# MCU.net
KiCad netlist of a schematic drawn in Altium Designer
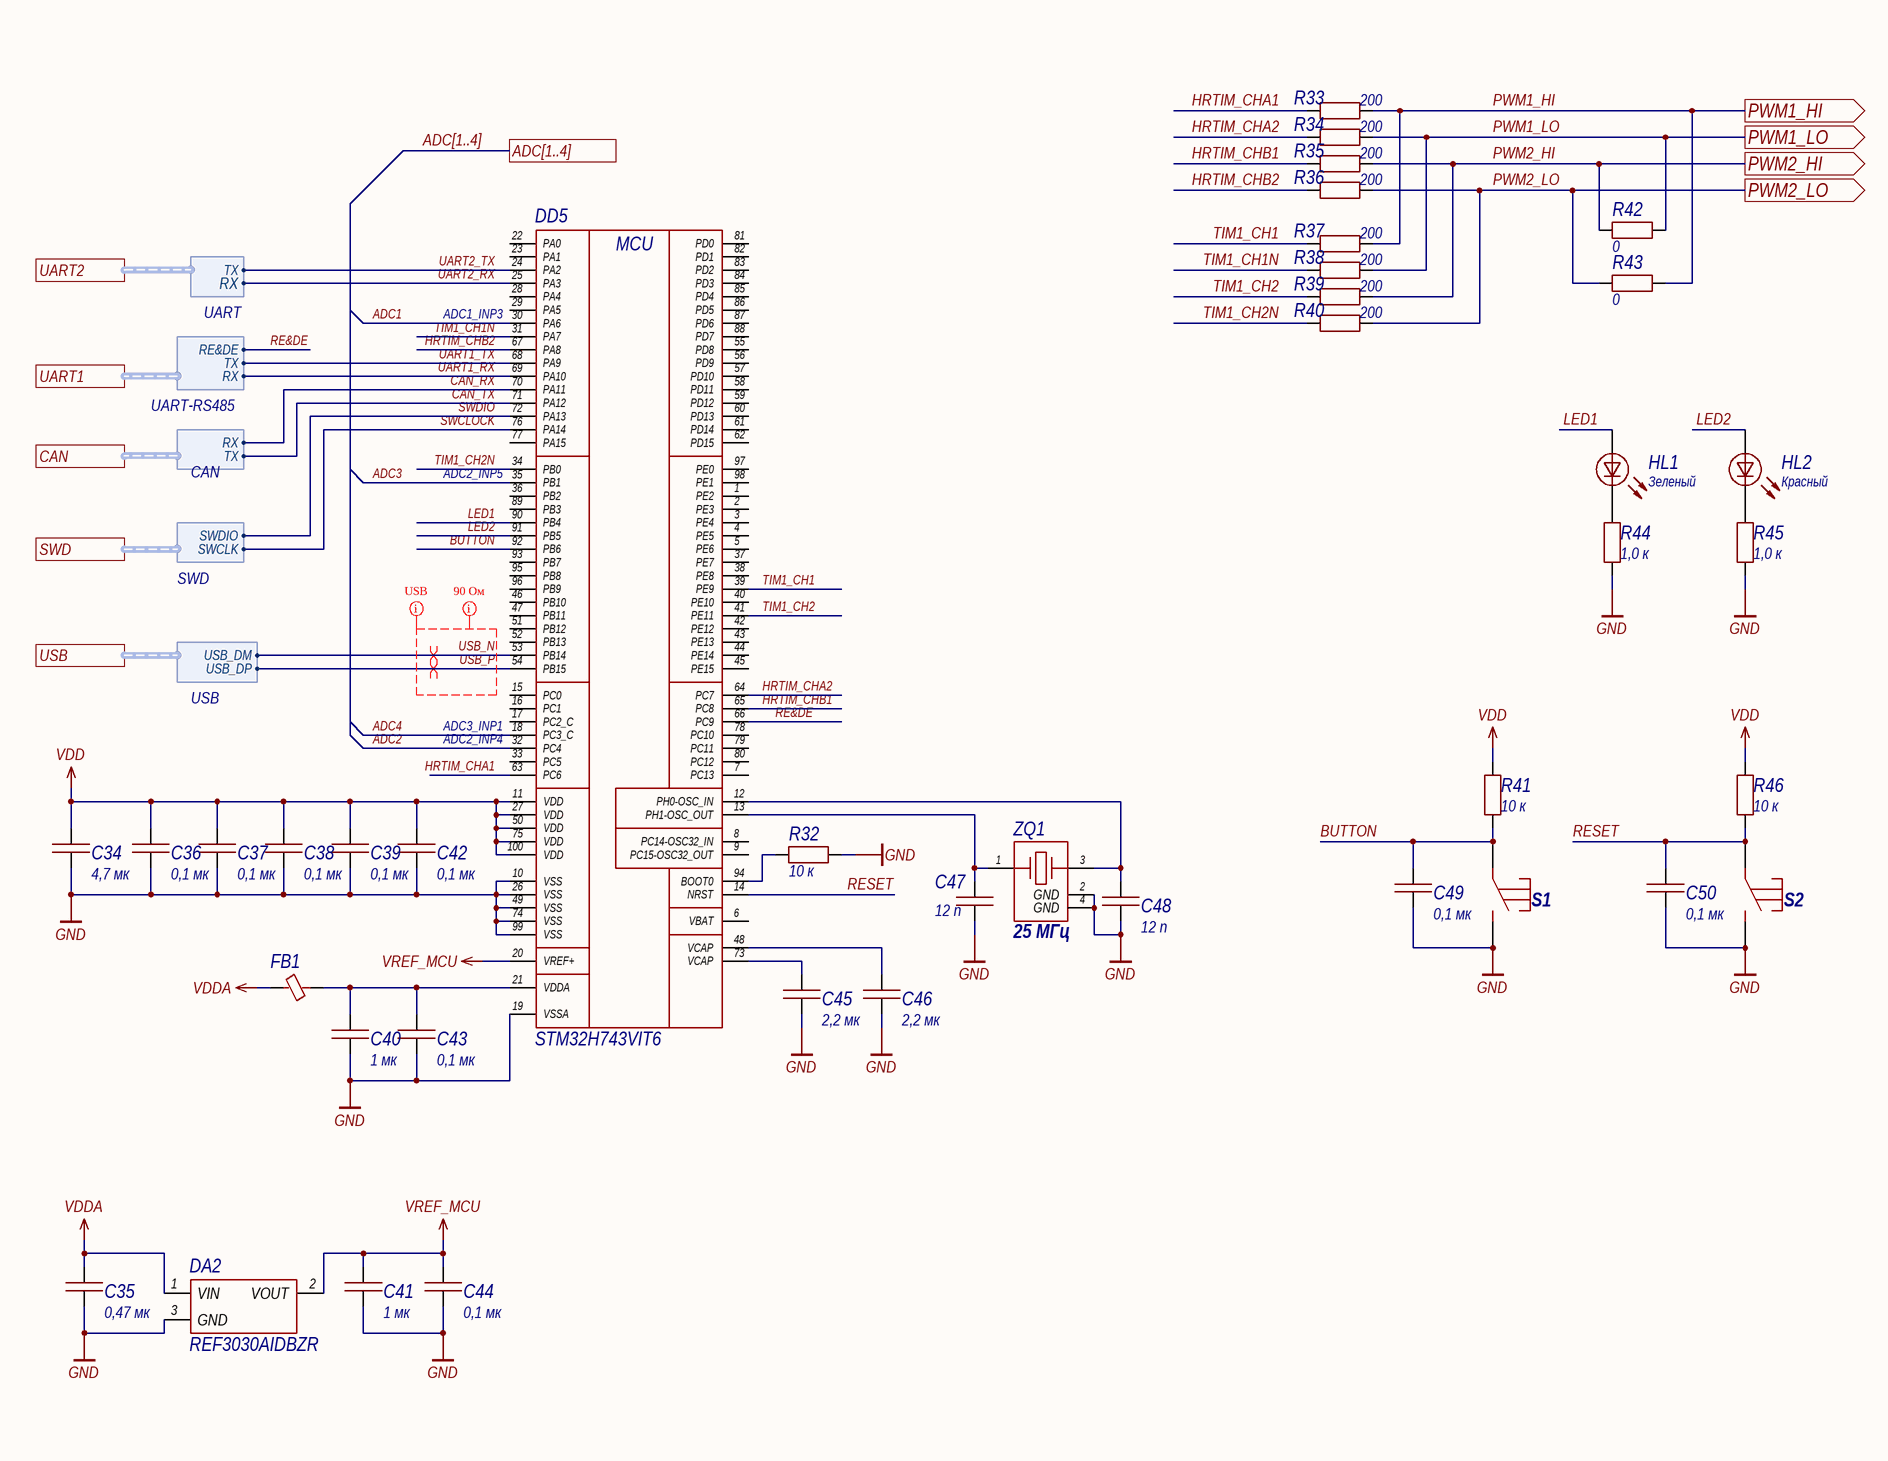
[diagram p0: MCU.SchDoc, left]
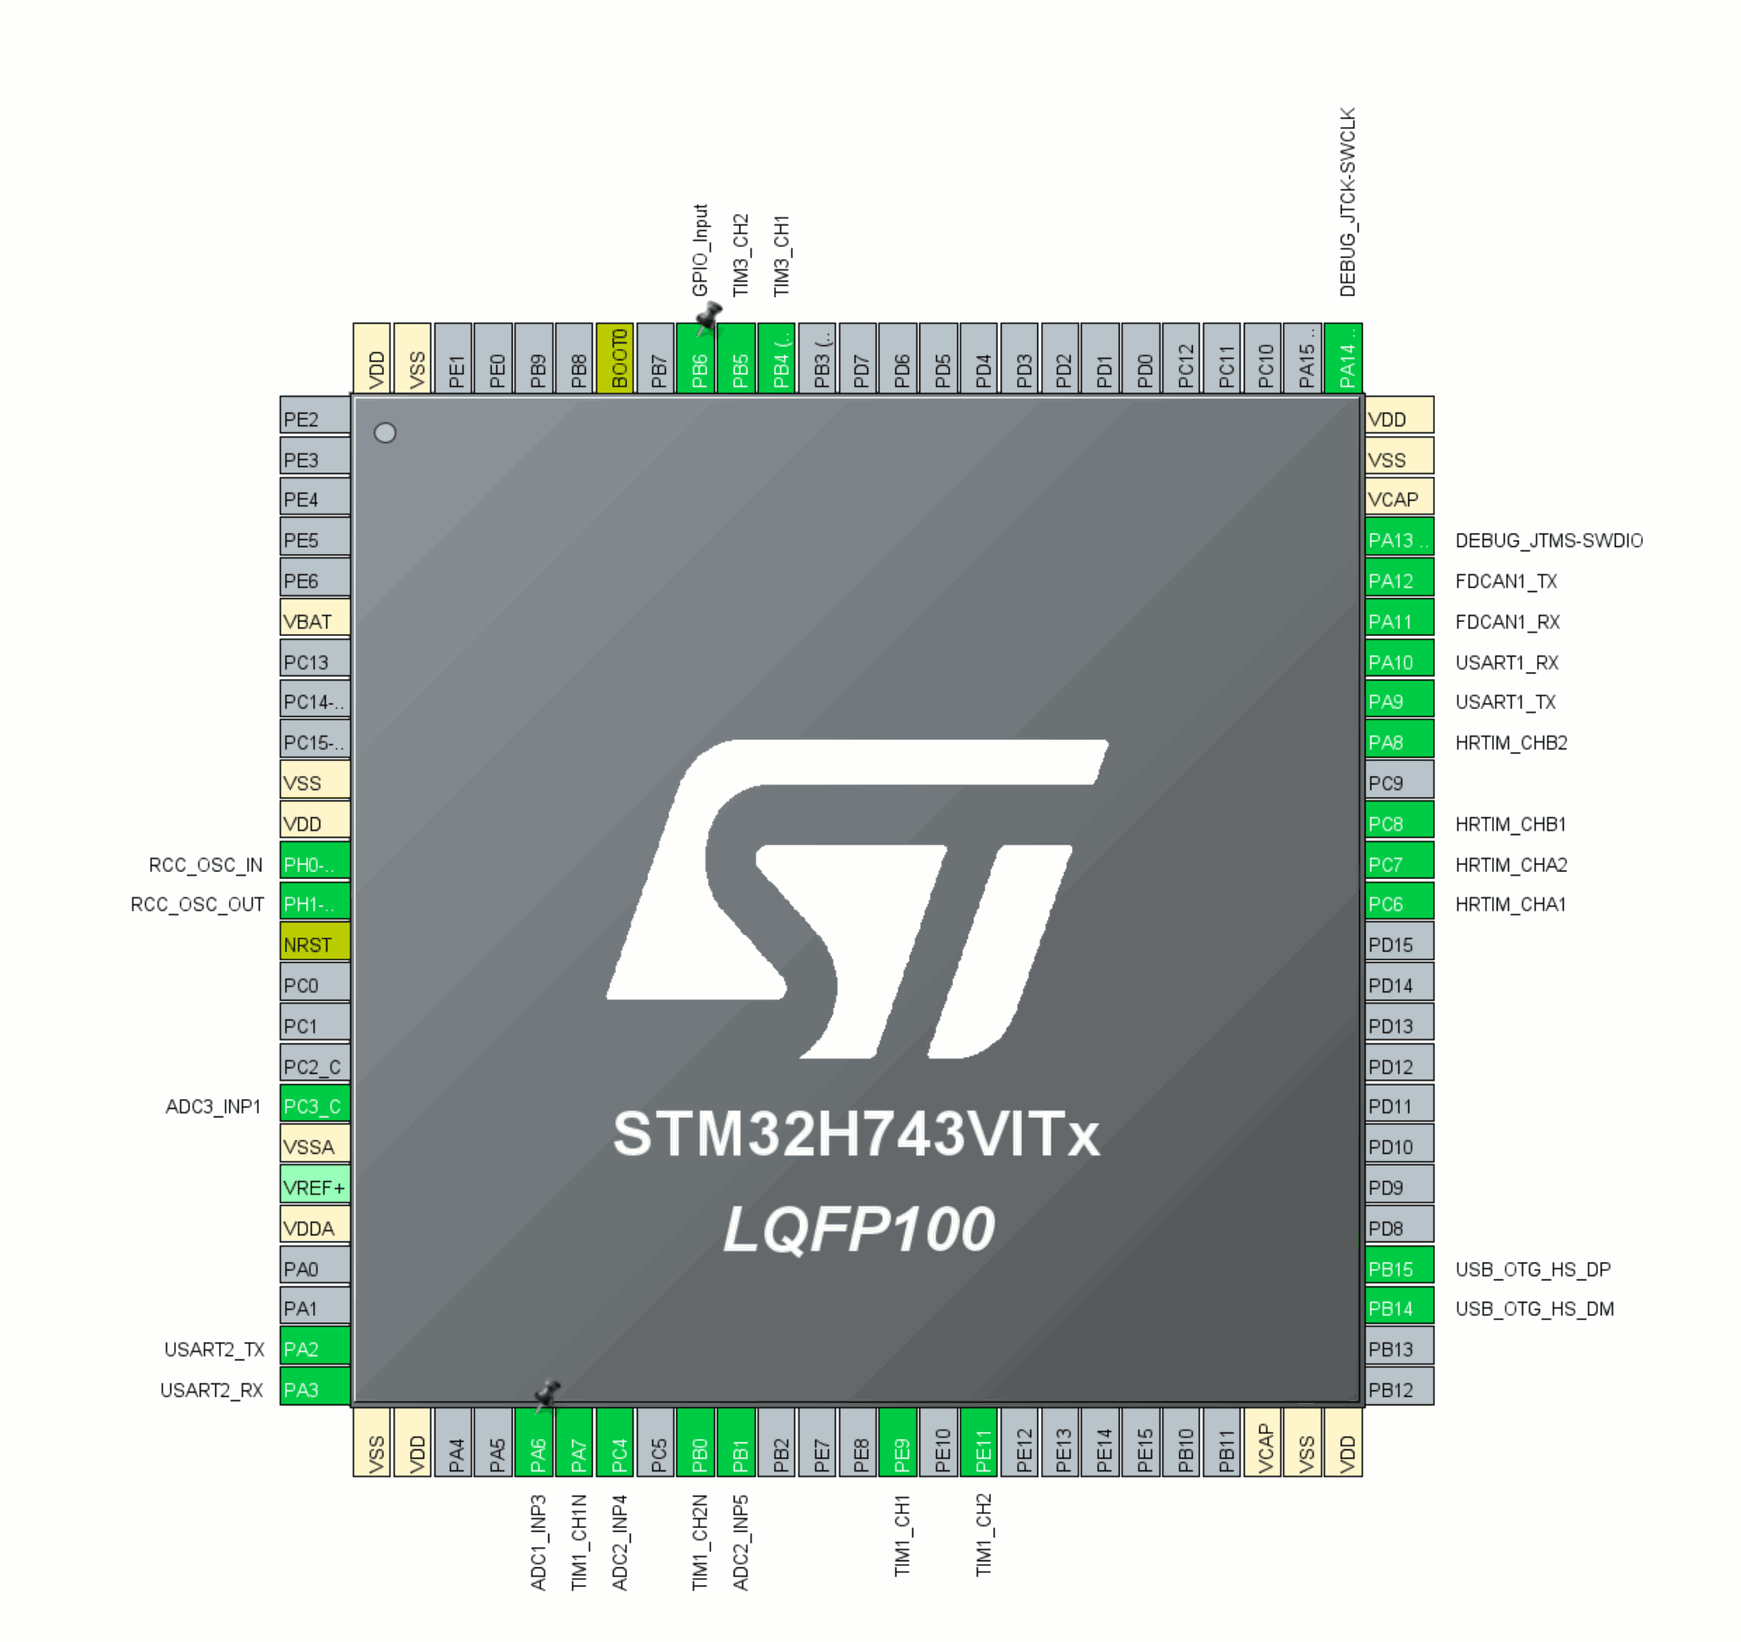
[diagram p1: MCU.SchDoc, right]

(export (version "E")
  (design (tool "Eeschema 10.0.6"))
  (components
    (comp (ref "C34")
      (value "4,7 мк")
      (footprint "1206C")
      (description "Конденсатор 1206C ёмкостью 4,7 мк 10%, 50 В, X7R")
      (fields (field (name "PART NUMBER") "Capacitor_4,7u_10_50V_X7R_1206C") (field (name "TOLERANCE") "10%"))
      (libsource (lib "Hydrolib") (part "Capacitor"))
    )
    (comp (ref "C35")
      (value "0,47 мк")
      (footprint "0603C")
      (description "Конденсатор 0603C ёмкостью 0,47 мк 10%, 50 В, X7R")
      (fields
        (field (name "PART NUMBER") "Capacitor_0,47u_10_50V_X7R_0603C")
        (field (name "TOLERANCE") "10%")
      )
      (libsource (lib "Hydrolib") (part "Capacitor"))
    )
    (comp (ref "C36")
      (value "0,1 мк")
      (footprint "0603C")
      (description "Конденсатор 0603C ёмкостью 0,1 мк 10%, 50 В, X7R")
      (fields (field (name "PART NUMBER") "Capacitor_0,1u_10_50V_X7R_0603C") (field (name "TOLERANCE") "10%"))
      (libsource (lib "Hydrolib") (part "Capacitor"))
    )
    (comp (ref "C37")
      (value "0,1 мк")
      (footprint "0603C")
      (description "Конденсатор 0603C ёмкостью 0,1 мк 10%, 50 В, X7R")
      (fields (field (name "PART NUMBER") "Capacitor_0,1u_10_50V_X7R_0603C") (field (name "TOLERANCE") "10%"))
      (libsource (lib "Hydrolib") (part "Capacitor"))
    )
    (comp (ref "C38")
      (value "0,1 мк")
      (footprint "0603C")
      (description "Конденсатор 0603C ёмкостью 0,1 мк 10%, 50 В, X7R")
      (fields (field (name "PART NUMBER") "Capacitor_0,1u_10_50V_X7R_0603C") (field (name "TOLERANCE") "10%"))
      (libsource (lib "Hydrolib") (part "Capacitor"))
    )
    (comp (ref "C39")
      (value "0,1 мк")
      (footprint "0603C")
      (description "Конденсатор 0603C ёмкостью 0,1 мк 10%, 50 В, X7R")
      (fields (field (name "PART NUMBER") "Capacitor_0,1u_10_50V_X7R_0603C") (field (name "TOLERANCE") "10%"))
      (libsource (lib "Hydrolib") (part "Capacitor"))
    )
    (comp (ref "C40")
      (value "1 мк")
      (footprint "0603C")
      (description "Конденсатор 0603C ёмкостью 1 мк 10%, 25 В, X7R")
      (fields (field (name "PART NUMBER") "Capacitor_1u_10_25V_X7R_0603C") (field (name "TOLERANCE") "10%"))
      (libsource (lib "Hydrolib") (part "Capacitor"))
    )
    (comp (ref "C41")
      (value "1 мк")
      (footprint "0603C")
      (description "Конденсатор 0603C ёмкостью 1 мк 10%, 25 В, X7R")
      (fields (field (name "PART NUMBER") "Capacitor_1u_10_25V_X7R_0603C") (field (name "TOLERANCE") "10%"))
      (libsource (lib "Hydrolib") (part "Capacitor"))
    )
    (comp (ref "C42")
      (value "0,1 мк")
      (footprint "0603C")
      (description "Конденсатор 0603C ёмкостью 0,1 мк 10%, 50 В, X7R")
      (fields (field (name "PART NUMBER") "Capacitor_0,1u_10_50V_X7R_0603C") (field (name "TOLERANCE") "10%"))
      (libsource (lib "Hydrolib") (part "Capacitor"))
    )
    (comp (ref "C43")
      (value "0,1 мк")
      (footprint "0603C")
      (description "Конденсатор 0603C ёмкостью 0,1 мк 10%, 50 В, X7R")
      (fields (field (name "PART NUMBER") "Capacitor_0,1u_10_50V_X7R_0603C") (field (name "TOLERANCE") "10%"))
      (libsource (lib "Hydrolib") (part "Capacitor"))
    )
    (comp (ref "C44")
      (value "0,1 мк")
      (footprint "0603C")
      (description "Конденсатор 0603C ёмкостью 0,1 мк 10%, 50 В, X7R")
      (fields (field (name "PART NUMBER") "Capacitor_0,1u_10_50V_X7R_0603C") (field (name "TOLERANCE") "10%"))
      (libsource (lib "Hydrolib") (part "Capacitor"))
    )
    (comp (ref "C45")
      (value "2,2 мк")
      (footprint "1206C")
      (description "Конденсатор 1206C ёмкостью 2,2 мк 10%, 50 В, X7R")
      (fields (field (name "PART NUMBER") "Capacitor_2,2u_10_50V_X7R_1206C") (field (name "TOLERANCE") "10%"))
      (libsource (lib "Hydrolib") (part "Capacitor"))
    )
    (comp (ref "C46")
      (value "2,2 мк")
      (footprint "1206C")
      (description "Конденсатор 1206C ёмкостью 2,2 мк 10%, 50 В, X7R")
      (fields (field (name "PART NUMBER") "Capacitor_2,2u_10_50V_X7R_1206C") (field (name "TOLERANCE") "10%"))
      (libsource (lib "Hydrolib") (part "Capacitor"))
    )
    (comp (ref "C47")
      (value "12 п")
      (footprint "0603C")
      (description "Конденсатор 0603C ёмкостью 12 п 5%, 50 В, NP0")
      (fields
        (field (name "PART NUMBER") "Capacitor_12p_5_50V_NP0_0603C")
        (field (name "TOLERANCE") "5%")
        (field (name "АВТОР") "glebmih")
      )
      (libsource (lib "Hydrolib") (part "Capacitor"))
    )
    (comp (ref "C48")
      (value "12 п")
      (footprint "0603C")
      (description "Конденсатор 0603C ёмкостью 12 п 5%, 50 В, NP0")
      (fields
        (field (name "PART NUMBER") "Capacitor_12p_5_50V_NP0_0603C")
        (field (name "TOLERANCE") "5%")
        (field (name "АВТОР") "glebmih")
      )
      (libsource (lib "Hydrolib") (part "Capacitor"))
    )
    (comp (ref "C49")
      (value "0,1 мк")
      (footprint "0603C")
      (description "Конденсатор 0603C ёмкостью 0,1 мк 10%, 50 В, X7R")
      (fields (field (name "PART NUMBER") "Capacitor_0,1u_10_50V_X7R_0603C") (field (name "TOLERANCE") "10%"))
      (libsource (lib "Hydrolib") (part "Capacitor"))
    )
    (comp (ref "C50")
      (value "0,1 мк")
      (footprint "0603C")
      (description "Конденсатор 0603C ёмкостью 0,1 мк 10%, 50 В, X7R")
      (fields (field (name "PART NUMBER") "Capacitor_0,1u_10_50V_X7R_0603C") (field (name "TOLERANCE") "10%"))
      (libsource (lib "Hydrolib") (part "Capacitor"))
    )
    (comp (ref "DA2")
      (value "REF3030AIDBZR")
      (footprint "SOT23-3")
      (description "Источник опорного напряжения, 3В")
      (fields (field (name "АВТОР") "glebmih"))
      (libsource (lib "Hydrolib") (part "REF3030AIDBZR"))
    )
    (comp (ref "DD5")
      (value "STM32H743VIT6")
      (footprint "LQFP100")
      (description "Микроконтроллер, 32-Бит, Cortex-M7, 480МГц, 2Мб Flash, 1Мб SRAM, 82 I/O")
      (fields (field (name "MF") "STMicroelectronics") (field (name "АВТОР") "glebmih"))
      (libsource (lib "Hydrolib") (part "STM32H743VIT6"))
    )
    (comp (ref "FB1")
      (value "BLM18AG102SN1D")
      (footprint "0603L")
      (description "Дроссель подавления ЭМП")
      (fields (field (name "АВТОР") "glebmih"))
      (libsource (lib "Hydrolib") (part "Ferrite_bead"))
    )
    (comp (ref "HL1")
      (value "Зеленый")
      (footprint "0805D")
      (description "Светодиод")
      (fields (field (name "PART NUMBER") "LED"))
      (libsource (lib "Hydrolib") (part "LED"))
    )
    (comp (ref "HL2")
      (value "Красный")
      (footprint "0805D")
      (description "Светодиод")
      (fields (field (name "PART NUMBER") "LED"))
      (libsource (lib "Hydrolib") (part "LED"))
    )
    (comp (ref "R32")
      (value "10 к")
      (footprint "0603R")
      (description "Резистор номиналом 10 кОм 1%")
      (fields (field (name "PART NUMBER") "Resistor_10k_1_0603") (field (name "TOLERANCE") "1%"))
      (libsource (lib "") (part "Resistor_2"))
    )
    (comp (ref "R33")
      (value "200")
      (footprint "0603R")
      (description "Резистор номиналом 200 Ом 1%")
      (fields (field (name "PART NUMBER") "Resistor_200_1_0603") (field (name "TOLERANCE") "1%"))
      (libsource (lib "") (part "Resistor_1"))
    )
    (comp (ref "R34")
      (value "200")
      (footprint "0603R")
      (description "Резистор номиналом 200 Ом 1%")
      (fields (field (name "PART NUMBER") "Resistor_200_1_0603") (field (name "TOLERANCE") "1%"))
      (libsource (lib "") (part "Resistor_1"))
    )
    (comp (ref "R35")
      (value "200")
      (footprint "0603R")
      (description "Резистор номиналом 200 Ом 1%")
      (fields (field (name "PART NUMBER") "Resistor_200_1_0603") (field (name "TOLERANCE") "1%"))
      (libsource (lib "") (part "Resistor_1"))
    )
    (comp (ref "R36")
      (value "200")
      (footprint "0603R")
      (description "Резистор номиналом 200 Ом 1%")
      (fields (field (name "PART NUMBER") "Resistor_200_1_0603") (field (name "TOLERANCE") "1%"))
      (libsource (lib "") (part "Resistor_1"))
    )
    (comp (ref "R37")
      (value "200")
      (footprint "0603R")
      (description "Резистор номиналом 200 Ом 1%")
      (fields (field (name "PART NUMBER") "Resistor_200_1_0603") (field (name "TOLERANCE") "1%"))
      (libsource (lib "") (part "Resistor_1"))
    )
    (comp (ref "R38")
      (value "200")
      (footprint "0603R")
      (description "Резистор номиналом 200 Ом 1%")
      (fields (field (name "PART NUMBER") "Resistor_200_1_0603") (field (name "TOLERANCE") "1%"))
      (libsource (lib "") (part "Resistor_1"))
    )
    (comp (ref "R39")
      (value "200")
      (footprint "0603R")
      (description "Резистор номиналом 200 Ом 1%")
      (fields (field (name "PART NUMBER") "Resistor_200_1_0603") (field (name "TOLERANCE") "1%"))
      (libsource (lib "") (part "Resistor_1"))
    )
    (comp (ref "R40")
      (value "200")
      (footprint "0603R")
      (description "Резистор номиналом 200 Ом 1%")
      (fields (field (name "PART NUMBER") "Resistor_200_1_0603") (field (name "TOLERANCE") "1%"))
      (libsource (lib "") (part "Resistor_1"))
    )
    (comp (ref "R41")
      (value "10 к")
      (footprint "0603R")
      (description "Резистор номиналом 10 кОм 1%")
      (fields (field (name "PART NUMBER") "Resistor_10k_1_0603") (field (name "TOLERANCE") "1%"))
      (libsource (lib "Hydrolib") (part "Resistor"))
    )
    (comp (ref "R42")
      (value "0")
      (footprint "0603R")
      (description "Резистор номиналом 0 Ом 5%")
      (fields
        (field (name "PART NUMBER") "Resistor_0_5_0603")
        (field (name "TOLERANCE") "5%")
        (field (name "АВТОР") "glebmih")
      )
      (libsource (lib "") (part "Resistor_1"))
    )
    (comp (ref "R43")
      (value "0")
      (footprint "0603R")
      (description "Резистор номиналом 0 Ом 5%")
      (fields
        (field (name "PART NUMBER") "Resistor_0_5_0603")
        (field (name "TOLERANCE") "5%")
        (field (name "АВТОР") "glebmih")
      )
      (libsource (lib "") (part "Resistor_1"))
    )
    (comp (ref "R44")
      (value "1,0 к")
      (footprint "0603R")
      (description "Резистор номиналом 1,0 кОм 1%")
      (fields (field (name "PART NUMBER") "Resistor_1.0k_1_0603") (field (name "TOLERANCE") "1%"))
      (libsource (lib "Hydrolib") (part "Resistor"))
    )
    (comp (ref "R45")
      (value "1,0 к")
      (footprint "0603R")
      (description "Резистор номиналом 1,0 кОм 1%")
      (fields (field (name "PART NUMBER") "Resistor_1.0k_1_0603") (field (name "TOLERANCE") "1%"))
      (libsource (lib "Hydrolib") (part "Resistor"))
    )
    (comp (ref "R46")
      (value "10 к")
      (footprint "0603R")
      (description "Резистор номиналом 10 кОм 1%")
      (fields (field (name "PART NUMBER") "Resistor_10k_1_0603") (field (name "TOLERANCE") "1%"))
      (libsource (lib "Hydrolib") (part "Resistor"))
    )
    (comp (ref "S1")
      (value "TSS-TD-19XA-XTR")
      (footprint "TSS-TD-19XA-XTR")
      (description "Тактовая кнопка")
      (fields (field (name "АВТОР") "glebmih"))
      (libsource (lib "Hydrolib") (part "Tact_button"))
    )
    (comp (ref "S2")
      (value "TSS-TD-19XA-XTR")
      (footprint "TSS-TD-19XA-XTR")
      (description "Тактовая кнопка")
      (fields (field (name "АВТОР") "glebmih"))
      (libsource (lib "Hydrolib") (part "Tact_button"))
    )
    (comp (ref "ZQ1")
      (value "25 МГц")
      (footprint "X322525MOB4SI")
      (description "Кварцевый резонатор SMD 25 МГц ±10ppm SMD-3225_4P")
      (fields (field (name "PART NUMBER") "X322525MOB4SI") (field (name "АВТОР") "rreali"))
      (libsource (lib "Hydrolib") (part "XTAL_1-3_GND"))
    )
  )
  (nets
    (net (code "6") (name "/ADC1") (class "Default")
      (node (ref "DD5") (pin "30") (pinfunction "PA6_30") (pintype "passive"))
    )
    (net (code "7") (name "/ADC2") (class "Default")
      (node (ref "DD5") (pin "32") (pinfunction "PC4_32") (pintype "passive"))
    )
    (net (code "8") (name "/ADC3") (class "Default")
      (node (ref "DD5") (pin "35") (pinfunction "PB1_35") (pintype "passive"))
    )
    (net (code "9") (name "/ADC4") (class "Default")
      (node (ref "DD5") (pin "18") (pinfunction "PC3_C_18") (pintype "passive"))
    )
    (net (code "11") (name "/BUTTON") (class "Default")
      (node (ref "C49") (pin "2") (pinfunction "2_2") (pintype "passive"))
      (node (ref "DD5") (pin "92") (pinfunction "PB6_92") (pintype "passive"))
      (node (ref "R41") (pin "1") (pinfunction "1_1") (pintype "passive"))
      (node (ref "S1") (pin "1") (pinfunction "1_1") (pintype "passive"))
    )
    (net (code "12") (name "/CAN_RX") (class "Default")
      (node (ref "DD5") (pin "70") (pinfunction "PA11_70") (pintype "passive"))
    )
    (net (code "13") (name "/CAN_TX") (class "Default")
      (node (ref "DD5") (pin "71") (pinfunction "PA12_71") (pintype "passive"))
    )
    (net (code "14") (name "/HRTIM_CHA1") (class "Default")
      (node (ref "DD5") (pin "63") (pinfunction "PC6_63") (pintype "passive"))
      (node (ref "R33") (pin "1") (pinfunction "1_1") (pintype "passive"))
    )
    (net (code "15") (name "/HRTIM_CHA2") (class "Default")
      (node (ref "DD5") (pin "64") (pinfunction "PC7_64") (pintype "passive"))
      (node (ref "R34") (pin "1") (pinfunction "1_1") (pintype "passive"))
    )
    (net (code "16") (name "/HRTIM_CHB1") (class "Default")
      (node (ref "DD5") (pin "65") (pinfunction "PC8_65") (pintype "passive"))
      (node (ref "R35") (pin "1") (pinfunction "1_1") (pintype "passive"))
    )
    (net (code "17") (name "/HRTIM_CHB2") (class "Default")
      (node (ref "DD5") (pin "67") (pinfunction "PA8_67") (pintype "passive"))
      (node (ref "R36") (pin "1") (pinfunction "1_1") (pintype "passive"))
    )
    (net (code "18") (name "/LED1") (class "Default")
      (node (ref "DD5") (pin "90") (pinfunction "PB4_90") (pintype "passive"))
      (node (ref "HL1") (pin "1") (pinfunction "1_1") (pintype "passive"))
    )
    (net (code "19") (name "/LED2") (class "Default")
      (node (ref "DD5") (pin "91") (pinfunction "PB5_91") (pintype "passive"))
      (node (ref "HL2") (pin "1") (pinfunction "1_1") (pintype "passive"))
    )
    (net (code "20") (name "/PWM1_HI") (class "Default")
      (node (ref "R33") (pin "2") (pinfunction "2_2") (pintype "passive"))
      (node (ref "R37") (pin "2") (pinfunction "2_2") (pintype "passive"))
      (node (ref "R43") (pin "2") (pinfunction "2_2") (pintype "passive"))
    )
    (net (code "21") (name "/PWM1_LO") (class "Default")
      (node (ref "R34") (pin "2") (pinfunction "2_2") (pintype "passive"))
      (node (ref "R38") (pin "2") (pinfunction "2_2") (pintype "passive"))
      (node (ref "R42") (pin "2") (pinfunction "2_2") (pintype "passive"))
    )
    (net (code "22") (name "/PWM2_HI") (class "Default")
      (node (ref "R35") (pin "2") (pinfunction "2_2") (pintype "passive"))
      (node (ref "R39") (pin "2") (pinfunction "2_2") (pintype "passive"))
      (node (ref "R42") (pin "1") (pinfunction "1_1") (pintype "passive"))
    )
    (net (code "23") (name "/PWM2_LO") (class "Default")
      (node (ref "R36") (pin "2") (pinfunction "2_2") (pintype "passive"))
      (node (ref "R40") (pin "2") (pinfunction "2_2") (pintype "passive"))
      (node (ref "R43") (pin "1") (pinfunction "1_1") (pintype "passive"))
    )
    (net (code "24") (name "/RE&DE") (class "Default")
      (node (ref "DD5") (pin "66") (pinfunction "PC9_66") (pintype "passive"))
    )
    (net (code "25") (name "/RESET") (class "Default")
      (node (ref "C50") (pin "2") (pinfunction "2_2") (pintype "passive"))
      (node (ref "DD5") (pin "14") (pinfunction "NRST_14") (pintype "passive"))
      (node (ref "R46") (pin "1") (pinfunction "1_1") (pintype "passive"))
      (node (ref "S2") (pin "1") (pinfunction "1_1") (pintype "passive"))
    )
    (net (code "26") (name "/SWCLOCK") (class "Default")
      (node (ref "DD5") (pin "76") (pinfunction "PA14_76") (pintype "passive"))
    )
    (net (code "27") (name "/SWDIO") (class "Default")
      (node (ref "DD5") (pin "72") (pinfunction "PA13_72") (pintype "passive"))
    )
    (net (code "28") (name "/TIM1_CH1") (class "Default")
      (node (ref "DD5") (pin "39") (pinfunction "PE9_39") (pintype "passive"))
      (node (ref "R37") (pin "1") (pinfunction "1_1") (pintype "passive"))
    )
    (net (code "29") (name "/TIM1_CH1N") (class "Default")
      (node (ref "DD5") (pin "31") (pinfunction "PA7_31") (pintype "passive"))
      (node (ref "R38") (pin "1") (pinfunction "1_1") (pintype "passive"))
    )
    (net (code "30") (name "/TIM1_CH2") (class "Default")
      (node (ref "DD5") (pin "41") (pinfunction "PE11_41") (pintype "passive"))
      (node (ref "R39") (pin "1") (pinfunction "1_1") (pintype "passive"))
    )
    (net (code "31") (name "/TIM1_CH2N") (class "Default")
      (node (ref "DD5") (pin "34") (pinfunction "PB0_34") (pintype "passive"))
      (node (ref "R40") (pin "1") (pinfunction "1_1") (pintype "passive"))
    )
    (net (code "32") (name "/UART1_RX") (class "Default")
      (node (ref "DD5") (pin "69") (pinfunction "PA10_69") (pintype "passive"))
    )
    (net (code "33") (name "/UART1_TX") (class "Default")
      (node (ref "DD5") (pin "68") (pinfunction "PA9_68") (pintype "passive"))
    )
    (net (code "34") (name "/UART2_RX") (class "Default")
      (node (ref "DD5") (pin "25") (pinfunction "PA3_25") (pintype "passive"))
    )
    (net (code "35") (name "/UART2_TX") (class "Default")
      (node (ref "DD5") (pin "24") (pinfunction "PA2_24") (pintype "passive"))
    )
    (net (code "36") (name "/USB_N") (class "Default")
      (node (ref "DD5") (pin "53") (pinfunction "PB14_53") (pintype "passive"))
    )
    (net (code "37") (name "/USB_P") (class "Default")
      (node (ref "DD5") (pin "54") (pinfunction "PB15_54") (pintype "passive"))
    )
    (net (code "43") (name "GND") (class "Default")
      (node (ref "C34") (pin "1") (pinfunction "1_1") (pintype "passive"))
      (node (ref "C35") (pin "1") (pinfunction "1_1") (pintype "passive"))
      (node (ref "C36") (pin "1") (pinfunction "1_1") (pintype "passive"))
      (node (ref "C37") (pin "1") (pinfunction "1_1") (pintype "passive"))
      (node (ref "C38") (pin "1") (pinfunction "1_1") (pintype "passive"))
      (node (ref "C39") (pin "1") (pinfunction "1_1") (pintype "passive"))
      (node (ref "C40") (pin "1") (pinfunction "1_1") (pintype "passive"))
      (node (ref "C41") (pin "1") (pinfunction "1_1") (pintype "passive"))
      (node (ref "C42") (pin "1") (pinfunction "1_1") (pintype "passive"))
      (node (ref "C43") (pin "1") (pinfunction "1_1") (pintype "passive"))
      (node (ref "C44") (pin "1") (pinfunction "1_1") (pintype "passive"))
      (node (ref "C45") (pin "1") (pinfunction "1_1") (pintype "passive"))
      (node (ref "C46") (pin "1") (pinfunction "1_1") (pintype "passive"))
      (node (ref "C47") (pin "1") (pinfunction "1_1") (pintype "passive"))
      (node (ref "C48") (pin "1") (pinfunction "1_1") (pintype "passive"))
      (node (ref "C49") (pin "1") (pinfunction "1_1") (pintype "passive"))
      (node (ref "C50") (pin "1") (pinfunction "1_1") (pintype "passive"))
      (node (ref "DA2") (pin "3") (pinfunction "GND_3") (pintype "passive"))
      (node (ref "DD5") (pin "10") (pinfunction "VSS_10") (pintype "power_in"))
      (node (ref "DD5") (pin "19") (pinfunction "VSSA_19") (pintype "power_in"))
      (node (ref "DD5") (pin "26") (pinfunction "VSS_26") (pintype "power_in"))
      (node (ref "DD5") (pin "49") (pinfunction "VSS_49") (pintype "power_in"))
      (node (ref "DD5") (pin "74") (pinfunction "VSS_74") (pintype "power_in"))
      (node (ref "DD5") (pin "99") (pinfunction "VSS_99") (pintype "power_in"))
      (node (ref "R32") (pin "1") (pinfunction "1_1") (pintype "passive"))
      (node (ref "R44") (pin "1") (pinfunction "1_1") (pintype "passive"))
      (node (ref "R45") (pin "1") (pinfunction "1_1") (pintype "passive"))
      (node (ref "S1") (pin "2") (pinfunction "2_2") (pintype "passive"))
      (node (ref "S2") (pin "2") (pinfunction "2_2") (pintype "passive"))
      (node (ref "ZQ1") (pin "2") (pinfunction "GND_2") (pintype "passive"))
      (node (ref "ZQ1") (pin "4") (pinfunction "GND_4") (pintype "passive"))
    )
    (net (code "44") (name "Net-(C45-Pad2)") (class "Default")
      (node (ref "C45") (pin "2") (pinfunction "2_2") (pintype "passive"))
      (node (ref "DD5") (pin "73") (pinfunction "VCAP_73") (pintype "power_in"))
    )
    (net (code "45") (name "Net-(C46-Pad2)") (class "Default")
      (node (ref "C46") (pin "2") (pinfunction "2_2") (pintype "passive"))
      (node (ref "DD5") (pin "48") (pinfunction "VCAP_48") (pintype "power_in"))
    )
    (net (code "46") (name "Net-(DD5-BOOT0)") (class "Default")
      (node (ref "DD5") (pin "94") (pinfunction "BOOT0_94") (pintype "passive"))
      (node (ref "R32") (pin "2") (pinfunction "2_2") (pintype "passive"))
    )
    (net (code "47") (name "Net-(DD5-PH0-OSC_IN)") (class "Default")
      (node (ref "C48") (pin "2") (pinfunction "2_2") (pintype "passive"))
      (node (ref "DD5") (pin "12") (pinfunction "PH0-OSC_IN_12") (pintype "passive"))
      (node (ref "ZQ1") (pin "3") (pinfunction "3_3") (pintype "passive"))
    )
    (net (code "48") (name "Net-(DD5-PH1-OSC_OUT)") (class "Default")
      (node (ref "C47") (pin "2") (pinfunction "2_2") (pintype "passive"))
      (node (ref "DD5") (pin "13") (pinfunction "PH1-OSC_OUT_13") (pintype "passive"))
      (node (ref "ZQ1") (pin "1") (pinfunction "1_1") (pintype "passive"))
    )
    (net (code "49") (name "Net-(DD5-VDDA)") (class "Default")
      (node (ref "C40") (pin "2") (pinfunction "2_2") (pintype "passive"))
      (node (ref "C43") (pin "2") (pinfunction "2_2") (pintype "passive"))
      (node (ref "DD5") (pin "21") (pinfunction "VDDA_21") (pintype "power_in"))
      (node (ref "FB1") (pin "2") (pinfunction "2_2") (pintype "passive"))
    )
    (net (code "50") (name "Net-(HL1-Pad2)") (class "Default")
      (node (ref "HL1") (pin "2") (pinfunction "2_2") (pintype "passive"))
      (node (ref "R44") (pin "2") (pinfunction "2_2") (pintype "passive"))
    )
    (net (code "51") (name "Net-(HL2-Pad2)") (class "Default")
      (node (ref "HL2") (pin "2") (pinfunction "2_2") (pintype "passive"))
      (node (ref "R45") (pin "2") (pinfunction "2_2") (pintype "passive"))
    )
    (net (code "52") (name "VDD") (class "Default")
      (node (ref "C34") (pin "2") (pinfunction "2_2") (pintype "passive"))
      (node (ref "C36") (pin "2") (pinfunction "2_2") (pintype "passive"))
      (node (ref "C37") (pin "2") (pinfunction "2_2") (pintype "passive"))
      (node (ref "C38") (pin "2") (pinfunction "2_2") (pintype "passive"))
      (node (ref "C39") (pin "2") (pinfunction "2_2") (pintype "passive"))
      (node (ref "C42") (pin "2") (pinfunction "2_2") (pintype "passive"))
      (node (ref "DD5") (pin "100") (pinfunction "VDD_100") (pintype "power_in"))
      (node (ref "DD5") (pin "11") (pinfunction "VDD_11") (pintype "power_in"))
      (node (ref "DD5") (pin "27") (pinfunction "VDD_27") (pintype "power_in"))
      (node (ref "DD5") (pin "50") (pinfunction "VDD_50") (pintype "power_in"))
      (node (ref "DD5") (pin "75") (pinfunction "VDD_75") (pintype "power_in"))
      (node (ref "R41") (pin "2") (pinfunction "2_2") (pintype "passive"))
      (node (ref "R46") (pin "2") (pinfunction "2_2") (pintype "passive"))
    )
    (net (code "53") (name "VDDA") (class "Default")
      (node (ref "C35") (pin "2") (pinfunction "2_2") (pintype "passive"))
      (node (ref "DA2") (pin "1") (pinfunction "VIN_1") (pintype "passive"))
      (node (ref "FB1") (pin "1") (pinfunction "1_1") (pintype "passive"))
    )
    (net (code "54") (name "VREF_MCU") (class "Default")
      (node (ref "C41") (pin "2") (pinfunction "2_2") (pintype "passive"))
      (node (ref "C44") (pin "2") (pinfunction "2_2") (pintype "passive"))
      (node (ref "DA2") (pin "2") (pinfunction "VOUT_2") (pintype "passive"))
      (node (ref "DD5") (pin "20") (pinfunction "VREF+_20") (pintype "power_in"))
    )
    (net (code "55") (name "unconnected-(DD5-PA0-Pad22)") (class "Default")
      (node (ref "DD5") (pin "22") (pinfunction "PA0_22") (pintype "passive"))
    )
    (net (code "56") (name "unconnected-(DD5-PA1-Pad23)") (class "Default")
      (node (ref "DD5") (pin "23") (pinfunction "PA1_23") (pintype "passive"))
    )
    (net (code "57") (name "unconnected-(DD5-PA4-Pad28)") (class "Default")
      (node (ref "DD5") (pin "28") (pinfunction "PA4_28") (pintype "passive"))
    )
    (net (code "58") (name "unconnected-(DD5-PA5-Pad29)") (class "Default")
      (node (ref "DD5") (pin "29") (pinfunction "PA5_29") (pintype "passive"))
    )
    (net (code "59") (name "unconnected-(DD5-PA15-Pad77)") (class "Default")
      (node (ref "DD5") (pin "77") (pinfunction "PA15_77") (pintype "passive"))
    )
    (net (code "60") (name "unconnected-(DD5-PB2-Pad36)") (class "Default")
      (node (ref "DD5") (pin "36") (pinfunction "PB2_36") (pintype "passive"))
    )
    (net (code "61") (name "unconnected-(DD5-PB3-Pad89)") (class "Default")
      (node (ref "DD5") (pin "89") (pinfunction "PB3_89") (pintype "passive"))
    )
    (net (code "62") (name "unconnected-(DD5-PB7-Pad93)") (class "Default")
      (node (ref "DD5") (pin "93") (pinfunction "PB7_93") (pintype "passive"))
    )
    (net (code "63") (name "unconnected-(DD5-PB8-Pad95)") (class "Default")
      (node (ref "DD5") (pin "95") (pinfunction "PB8_95") (pintype "passive"))
    )
    (net (code "64") (name "unconnected-(DD5-PB9-Pad96)") (class "Default")
      (node (ref "DD5") (pin "96") (pinfunction "PB9_96") (pintype "passive"))
    )
    (net (code "65") (name "unconnected-(DD5-PB10-Pad46)") (class "Default")
      (node (ref "DD5") (pin "46") (pinfunction "PB10_46") (pintype "passive"))
    )
    (net (code "66") (name "unconnected-(DD5-PB11-Pad47)") (class "Default")
      (node (ref "DD5") (pin "47") (pinfunction "PB11_47") (pintype "passive"))
    )
    (net (code "67") (name "unconnected-(DD5-PB12-Pad51)") (class "Default")
      (node (ref "DD5") (pin "51") (pinfunction "PB12_51") (pintype "passive"))
    )
    (net (code "68") (name "unconnected-(DD5-PB13-Pad52)") (class "Default")
      (node (ref "DD5") (pin "52") (pinfunction "PB13_52") (pintype "passive"))
    )
    (net (code "69") (name "unconnected-(DD5-PC0-Pad15)") (class "Default")
      (node (ref "DD5") (pin "15") (pinfunction "PC0_15") (pintype "passive"))
    )
    (net (code "70") (name "unconnected-(DD5-PC1-Pad16)") (class "Default")
      (node (ref "DD5") (pin "16") (pinfunction "PC1_16") (pintype "passive"))
    )
    (net (code "71") (name "unconnected-(DD5-PC2_C-Pad17)") (class "Default")
      (node (ref "DD5") (pin "17") (pinfunction "PC2_C_17") (pintype "passive"))
    )
    (net (code "72") (name "unconnected-(DD5-PC5-Pad33)") (class "Default")
      (node (ref "DD5") (pin "33") (pinfunction "PC5_33") (pintype "passive"))
    )
    (net (code "73") (name "unconnected-(DD5-PC10-Pad78)") (class "Default")
      (node (ref "DD5") (pin "78") (pinfunction "PC10_78") (pintype "passive"))
    )
    (net (code "74") (name "unconnected-(DD5-PC11-Pad79)") (class "Default")
      (node (ref "DD5") (pin "79") (pinfunction "PC11_79") (pintype "passive"))
    )
    (net (code "75") (name "unconnected-(DD5-PC12-Pad80)") (class "Default")
      (node (ref "DD5") (pin "80") (pinfunction "PC12_80") (pintype "passive"))
    )
    (net (code "76") (name "unconnected-(DD5-PC13-Pad7)") (class "Default")
      (node (ref "DD5") (pin "7") (pinfunction "PC13_7") (pintype "passive"))
    )
    (net (code "77") (name "unconnected-(DD5-PC14-OSC32_IN-Pad8)") (class "Default")
      (node (ref "DD5") (pin "8") (pinfunction "PC14-OSC32_IN_8") (pintype "passive"))
    )
    (net (code "78") (name "unconnected-(DD5-PC15-OSC32_OUT-Pad9)") (class "Default")
      (node (ref "DD5") (pin "9") (pinfunction "PC15-OSC32_OUT_9") (pintype "passive"))
    )
    (net (code "79") (name "unconnected-(DD5-PD0-Pad81)") (class "Default")
      (node (ref "DD5") (pin "81") (pinfunction "PD0_81") (pintype "passive"))
    )
    (net (code "80") (name "unconnected-(DD5-PD1-Pad82)") (class "Default")
      (node (ref "DD5") (pin "82") (pinfunction "PD1_82") (pintype "passive"))
    )
    (net (code "81") (name "unconnected-(DD5-PD2-Pad83)") (class "Default")
      (node (ref "DD5") (pin "83") (pinfunction "PD2_83") (pintype "passive"))
    )
    (net (code "82") (name "unconnected-(DD5-PD3-Pad84)") (class "Default")
      (node (ref "DD5") (pin "84") (pinfunction "PD3_84") (pintype "passive"))
    )
    (net (code "83") (name "unconnected-(DD5-PD4-Pad85)") (class "Default")
      (node (ref "DD5") (pin "85") (pinfunction "PD4_85") (pintype "passive"))
    )
    (net (code "84") (name "unconnected-(DD5-PD5-Pad86)") (class "Default")
      (node (ref "DD5") (pin "86") (pinfunction "PD5_86") (pintype "passive"))
    )
    (net (code "85") (name "unconnected-(DD5-PD6-Pad87)") (class "Default")
      (node (ref "DD5") (pin "87") (pinfunction "PD6_87") (pintype "passive"))
    )
    (net (code "86") (name "unconnected-(DD5-PD7-Pad88)") (class "Default")
      (node (ref "DD5") (pin "88") (pinfunction "PD7_88") (pintype "passive"))
    )
    (net (code "87") (name "unconnected-(DD5-PD8-Pad55)") (class "Default")
      (node (ref "DD5") (pin "55") (pinfunction "PD8_55") (pintype "passive"))
    )
    (net (code "88") (name "unconnected-(DD5-PD9-Pad56)") (class "Default")
      (node (ref "DD5") (pin "56") (pinfunction "PD9_56") (pintype "passive"))
    )
    (net (code "89") (name "unconnected-(DD5-PD10-Pad57)") (class "Default")
      (node (ref "DD5") (pin "57") (pinfunction "PD10_57") (pintype "passive"))
    )
    (net (code "90") (name "unconnected-(DD5-PD11-Pad58)") (class "Default")
      (node (ref "DD5") (pin "58") (pinfunction "PD11_58") (pintype "passive"))
    )
    (net (code "91") (name "unconnected-(DD5-PD12-Pad59)") (class "Default")
      (node (ref "DD5") (pin "59") (pinfunction "PD12_59") (pintype "passive"))
    )
    (net (code "92") (name "unconnected-(DD5-PD13-Pad60)") (class "Default")
      (node (ref "DD5") (pin "60") (pinfunction "PD13_60") (pintype "passive"))
    )
    (net (code "93") (name "unconnected-(DD5-PD14-Pad61)") (class "Default")
      (node (ref "DD5") (pin "61") (pinfunction "PD14_61") (pintype "passive"))
    )
    (net (code "94") (name "unconnected-(DD5-PD15-Pad62)") (class "Default")
      (node (ref "DD5") (pin "62") (pinfunction "PD15_62") (pintype "passive"))
    )
    (net (code "95") (name "unconnected-(DD5-PE0-Pad97)") (class "Default")
      (node (ref "DD5") (pin "97") (pinfunction "PE0_97") (pintype "passive"))
    )
    (net (code "96") (name "unconnected-(DD5-PE1-Pad98)") (class "Default")
      (node (ref "DD5") (pin "98") (pinfunction "PE1_98") (pintype "passive"))
    )
    (net (code "97") (name "unconnected-(DD5-PE2-Pad1)") (class "Default")
      (node (ref "DD5") (pin "1") (pinfunction "PE2_1") (pintype "passive"))
    )
    (net (code "98") (name "unconnected-(DD5-PE3-Pad2)") (class "Default")
      (node (ref "DD5") (pin "2") (pinfunction "PE3_2") (pintype "passive"))
    )
    (net (code "99") (name "unconnected-(DD5-PE4-Pad3)") (class "Default")
      (node (ref "DD5") (pin "3") (pinfunction "PE4_3") (pintype "passive"))
    )
    (net (code "100") (name "unconnected-(DD5-PE5-Pad4)") (class "Default")
      (node (ref "DD5") (pin "4") (pinfunction "PE5_4") (pintype "passive"))
    )
    (net (code "101") (name "unconnected-(DD5-PE6-Pad5)") (class "Default")
      (node (ref "DD5") (pin "5") (pinfunction "PE6_5") (pintype "passive"))
    )
    (net (code "102") (name "unconnected-(DD5-PE7-Pad37)") (class "Default")
      (node (ref "DD5") (pin "37") (pinfunction "PE7_37") (pintype "passive"))
    )
    (net (code "103") (name "unconnected-(DD5-PE8-Pad38)") (class "Default")
      (node (ref "DD5") (pin "38") (pinfunction "PE8_38") (pintype "passive"))
    )
    (net (code "104") (name "unconnected-(DD5-PE10-Pad40)") (class "Default")
      (node (ref "DD5") (pin "40") (pinfunction "PE10_40") (pintype "passive"))
    )
    (net (code "105") (name "unconnected-(DD5-PE12-Pad42)") (class "Default")
      (node (ref "DD5") (pin "42") (pinfunction "PE12_42") (pintype "passive"))
    )
    (net (code "106") (name "unconnected-(DD5-PE13-Pad43)") (class "Default")
      (node (ref "DD5") (pin "43") (pinfunction "PE13_43") (pintype "passive"))
    )
    (net (code "107") (name "unconnected-(DD5-PE14-Pad44)") (class "Default")
      (node (ref "DD5") (pin "44") (pinfunction "PE14_44") (pintype "passive"))
    )
    (net (code "108") (name "unconnected-(DD5-PE15-Pad45)") (class "Default")
      (node (ref "DD5") (pin "45") (pinfunction "PE15_45") (pintype "passive"))
    )
    (net (code "109") (name "unconnected-(DD5-VBAT-Pad6)") (class "Default")
      (node (ref "DD5") (pin "6") (pinfunction "VBAT_6") (pintype "passive"))
    )
  )
)
